# IR.net
KiCad netlist of a schematic drawn in Altium Designer
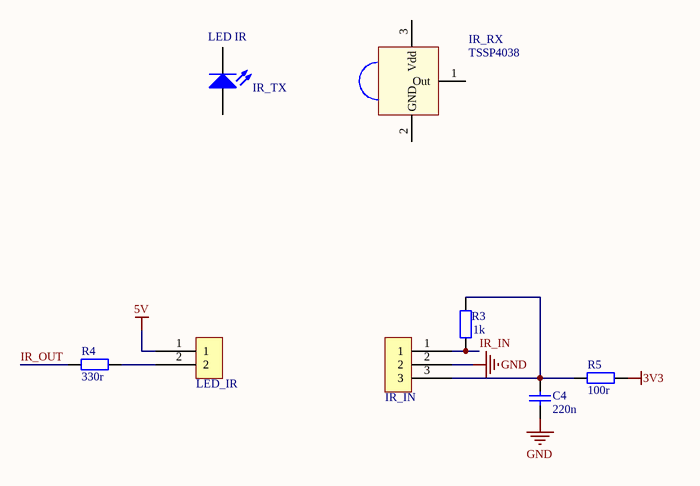
[diagram p0: IR.SchDoc]

(export (version "E")
  (design (tool "Eeschema 10.0.6"))
  (components
    (comp (ref "C4")
      (value "220n")
      (footprint "0805-C")
      (description "Condensateur céramique multicouche CMS, 0.22 µF, 50 V, 0805 [2012 Metric], ± 10%, X7R")
      (fields (field (name "VOLTAGE") "50V"))
      (libsource (lib "MGLib_v2") (part "Cap_np"))
    )
    (comp (ref "IR_IN")
      (value "Bornier_3_vis")
      (footprint "282834-3")
      (description "Bornier fil-à-carte, 2.54 mm, 3 Voies, 30 AWG, 16 AWG, 1.4 mm², Par vis")
      (fields (field (name "VOLTAGE") "150V"))
      (libsource (lib "MGLib_v2") (part "Bornier_3_vis"))
    )
    (comp (ref "IR_RX")
      (value "TSSP4038")
      (description "Récepteur infrarouge, Barrière lumineuse, 38 kHz, Traversant Vue latérale, 25m, 0.4 mW/m²")
      (libsource (lib "MGLib_v2") (part "TSSP93056"))
    )
    (comp (ref "IR_TX")
      (value "LED IR")
      (description "Emetteur infrarouge, Haute Puissance, 940 nm, 17 °, T-1 3/4 (5mm), 15 mW/Sr, 15 ns, 15 ns")
      (libsource (lib "MGLib_v2") (part "LED white"))
    )
    (comp (ref "LED_IR")
      (value "Bornier_2_vis")
      (footprint "282834-2")
      (description "Bornier fil-à-carte, 2.54 mm, 2 Voies, 30 AWG, 16 AWG, 1.4 mm², Par vis")
      (fields (field (name "VOLTAGE") "150V"))
      (libsource (lib "MGLib_v2") (part "Bornier_2_vis"))
    )
    (comp (ref "R3")
      (value "1k")
      (footprint "0805-R")
      (description "Résistance à puce CMS, Couche épaisse, 1 kohm, ± 1%, 125 mW, 0805 [2012 Metric], Couche épaisse")
      (libsource (lib "") (part "Res_1"))
    )
    (comp (ref "R4")
      (value "330r")
      (footprint "0805-R")
      (description "Résistance à puce CMS, Couche épaisse, 330 ohm, ± 1%, 125 mW, 0805 [2012 Metric], Couche épaisse")
      (fields (field (name "VOLTAGE") "150V"))
      (libsource (lib "MGLib_v2") (part "Res"))
    )
    (comp (ref "R5")
      (value "100r")
      (footprint "0805-R")
      (description "Résistance à puce CMS, 100 ohm, ± 1%, 500 mW, 0805 [2012 Metric], Couche épaisse, Anti-Surtension")
      (fields (field (name "VOLTAGE") "150V"))
      (libsource (lib "MGLib_v2") (part "Res"))
    )
  )
  (nets
    (net (code "1") (name "/IR_IN") (class "Default")
      (node (ref "IR_IN") (pin "1") (pinfunction "1_1") (pintype "passive"))
      (node (ref "R3") (pin "1") (pinfunction "1_1") (pintype "passive"))
    )
    (net (code "2") (name "/IR_OUT") (class "Default")
      (node (ref "R4") (pin "1") (pinfunction "1_1") (pintype "passive"))
    )
    (net (code "3") (name "3V3") (class "Default")
      (node (ref "R5") (pin "2") (pinfunction "2_2") (pintype "passive"))
    )
    (net (code "4") (name "5V") (class "Default")
      (node (ref "LED_IR") (pin "1") (pinfunction "1_1") (pintype "passive"))
    )
    (net (code "5") (name "GND") (class "Default")
      (node (ref "C4") (pin "1") (pinfunction "1_1") (pintype "passive"))
      (node (ref "IR_IN") (pin "2") (pinfunction "2_2") (pintype "passive"))
    )
    (net (code "6") (name "Net-(C4-Pad2)") (class "Default")
      (node (ref "C4") (pin "2") (pinfunction "2_2") (pintype "passive"))
      (node (ref "IR_IN") (pin "3") (pinfunction "3_3") (pintype "passive"))
      (node (ref "R3") (pin "2") (pinfunction "2_2") (pintype "passive"))
      (node (ref "R5") (pin "1") (pinfunction "1_1") (pintype "passive"))
    )
    (net (code "7") (name "Net-(LED_IR-Pad2)") (class "Default")
      (node (ref "LED_IR") (pin "2") (pinfunction "2_2") (pintype "passive"))
      (node (ref "R4") (pin "2") (pinfunction "2_2") (pintype "passive"))
    )
    (net (code "8") (name "unconnected-(IR_RX-GND-Pad2)") (class "Default")
      (node (ref "IR_RX") (pin "2") (pinfunction "GND_2") (pintype "passive"))
    )
    (net (code "9") (name "unconnected-(IR_RX-Out-Pad1)") (class "Default")
      (node (ref "IR_RX") (pin "1") (pinfunction "Out_1") (pintype "passive"))
    )
    (net (code "10") (name "unconnected-(IR_RX-Vdd-Pad3)") (class "Default")
      (node (ref "IR_RX") (pin "3") (pinfunction "Vdd_3") (pintype "passive"))
    )
    (net (code "11") (name "unconnected-(IR_TX-A-Pad2)") (class "Default")
      (node (ref "IR_TX") (pin "2") (pinfunction "A_2") (pintype "passive"))
    )
    (net (code "12") (name "unconnected-(IR_TX-K-Pad1)") (class "Default")
      (node (ref "IR_TX") (pin "1") (pinfunction "K_1") (pintype "passive"))
    )
  )
)
